# simCard.net
KiCad netlist of a schematic drawn in Altium Designer
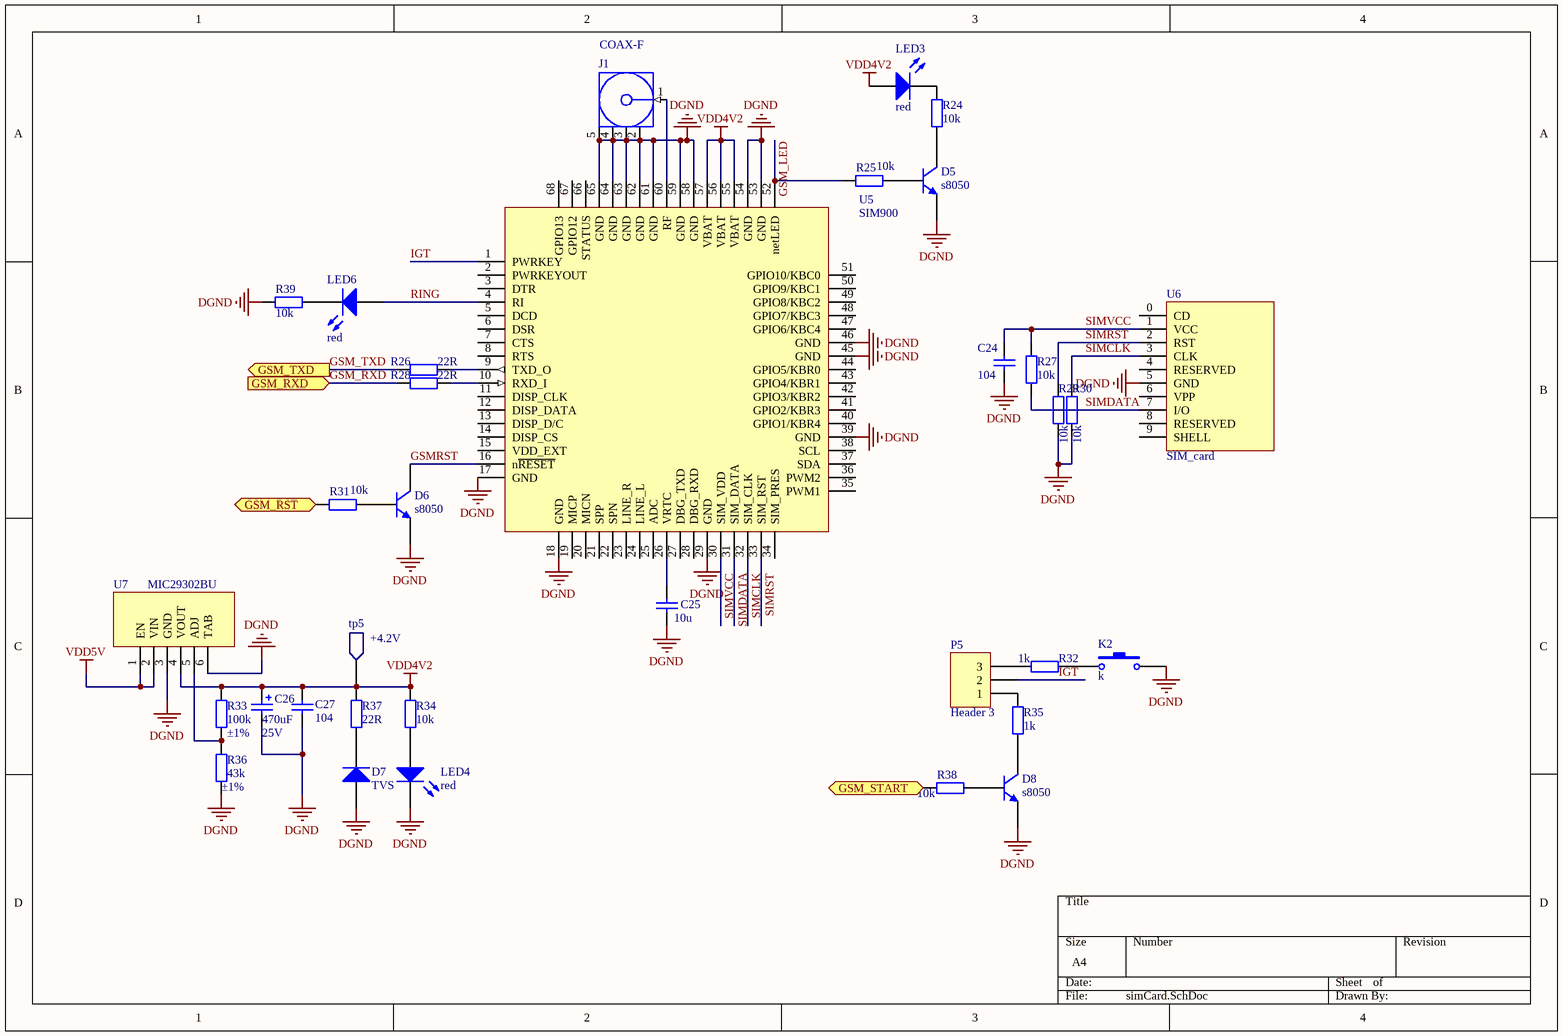
[diagram p0: simCard.SchDoc]

(export (version "E")
  (design (tool "Eeschema 10.0.6"))
  (components
    (comp (ref "C24") (value "104") (footprint "0603_") (libsource (lib "chxxlib") (part "cap")))
    (comp (ref "C25") (value "10u") (footprint "0603_") (libsource (lib "chxxlib") (part "cap")))
    (comp (ref "C26")
      (value "470uF")
      (footprint "Cap - 10mmx10mm")
      (fields (field (name "VDC_") "25V"))
      (libsource (lib "chxxlib") (part "cap-pol"))
    )
    (comp (ref "C27") (value "104") (footprint "0603_") (libsource (lib "chxxlib") (part "cap")))
    (comp (ref "D5") (value "s8050") (footprint "SOT-23(bce)") (libsource (lib "chxxlib") (part "NPN")))
    (comp (ref "D6") (value "s8050") (footprint "SOT-23(bce)") (libsource (lib "chxxlib") (part "NPN")))
    (comp (ref "D7") (value "TVS") (footprint "SMB") (libsource (lib "chxxlib") (part "diode")))
    (comp (ref "D8") (value "s8050") (footprint "SOT-23(bce)") (libsource (lib "chxxlib") (part "NPN")))
    (comp (ref "J1")
      (value "COAX-F")
      (footprint "MCX5.08-H5")
      (fields (field (name "PUBLISHER") "Altium Limited"))
      (libsource (lib "Miscellaneous Connectors") (part "COAX-F"))
    )
    (comp (ref "K2") (value "k") (footprint "key-2pin") (libsource (lib "chxxlib") (part "SW")))
    (comp (ref "LED3") (value "red") (footprint "0603_diode") (libsource (lib "chxxlib") (part "red")))
    (comp (ref "LED4") (value "red") (footprint "0603_diode") (libsource (lib "chxxlib") (part "red")))
    (comp (ref "LED6") (value "red") (footprint "0603_diode") (libsource (lib "chxxlib") (part "red")))
    (comp (ref "P5")
      (value "Header 3")
      (footprint "HDR1X3")
      (description "Header, 3-Pin")
      (fields (field (name "PUBLISHER") "Altium Limited"))
      (libsource (lib "Miscellaneous Connectors") (part "Header 3"))
    )
    (comp (ref "R24") (value "10k") (footprint "0603_") (libsource (lib "chxxlib") (part "res")))
    (comp (ref "R25") (value "10k") (footprint "0603_") (libsource (lib "") (part "res_2")))
    (comp (ref "R26") (value "22R") (footprint "0603_") (libsource (lib "") (part "res_1")))
    (comp (ref "R27") (value "10k") (footprint "0603_") (libsource (lib "chxxlib") (part "res")))
    (comp (ref "R28") (value "22R") (footprint "0603_") (libsource (lib "") (part "res_1")))
    (comp (ref "R29") (value "10k") (footprint "0603_") (libsource (lib "chxxlib") (part "res")))
    (comp (ref "R30") (value "10k") (footprint "0603_") (libsource (lib "chxxlib") (part "res")))
    (comp (ref "R31") (value "10k") (footprint "0603_") (libsource (lib "") (part "res_2")))
    (comp (ref "R32") (value "1k") (footprint "0603_") (libsource (lib "") (part "res_2")))
    (comp (ref "R33")
      (value "100k")
      (footprint "0603_")
      (fields (field (name "TOLERANCE_") "±1%"))
      (libsource (lib "chxxlib") (part "res"))
    )
    (comp (ref "R34") (value "10k") (footprint "0603_") (libsource (lib "chxxlib") (part "res")))
    (comp (ref "R35") (value "1k") (footprint "0603_") (libsource (lib "chxxlib") (part "res")))
    (comp (ref "R36")
      (value "43k")
      (footprint "0603_")
      (fields (field (name "TOLERANCE_") "±1%"))
      (libsource (lib "chxxlib") (part "res"))
    )
    (comp (ref "R37") (value "22R") (footprint "0603_") (libsource (lib "chxxlib") (part "res")))
    (comp (ref "R38") (value "10k") (footprint "0603_") (libsource (lib "") (part "res_2")))
    (comp (ref "R39") (value "10k") (footprint "0603_") (libsource (lib "") (part "res_1")))
    (comp (ref "tp5") (value "+4.2V") (footprint "testPoint") (libsource (lib "chxxlib") (part "pad")))
    (comp (ref "U5") (value "SIM900") (footprint "SIM900") (libsource (lib "chxxlib") (part "SIM900")))
    (comp (ref "U6") (value "SIM_card") (footprint "SIM_Card") (libsource (lib "chxxlib") (part "SIM_card")))
    (comp (ref "U7")
      (value "MIC29302BU")
      (footprint "TO-263(S)")
      (libsource (lib "chxxlib") (part "MIC29302BU"))
    )
  )
  (nets
    (net (code "1") (name "/GSMRST") (class "Default")
      (node (ref "D6") (pin "c") (pinfunction "C_c") (pintype "passive"))
      (node (ref "U5") (pin "16") (pinfunction "n~{RESET}_16") (pintype "passive"))
    )
    (net (code "2") (name "/GSM_LED") (class "Default")
      (node (ref "R25") (pin "2") (pinfunction "2_2") (pintype "passive"))
      (node (ref "U5") (pin "52") (pinfunction "netLED_52") (pintype "passive"))
    )
    (net (code "3") (name "/GSM_RST") (class "Default")
      (node (ref "R31") (pin "2") (pinfunction "2_2") (pintype "passive"))
    )
    (net (code "4") (name "/GSM_RXD") (class "Default")
      (node (ref "R28") (pin "1") (pinfunction "1_1") (pintype "passive"))
    )
    (net (code "5") (name "/GSM_START") (class "Default")
      (node (ref "R38") (pin "2") (pinfunction "2_2") (pintype "passive"))
    )
    (net (code "6") (name "/GSM_TXD") (class "Default")
      (node (ref "R26") (pin "1") (pinfunction "1_1") (pintype "passive"))
    )
    (net (code "7") (name "/IGT") (class "Default")
      (node (ref "P5") (pin "2") (pinfunction "2_2") (pintype "passive"))
      (node (ref "U5") (pin "1") (pinfunction "PWRKEY_1") (pintype "passive"))
    )
    (net (code "8") (name "/RING") (class "Default")
      (node (ref "LED6") (pin "1") (pinfunction "A_1") (pintype "passive"))
      (node (ref "U5") (pin "4") (pinfunction "RI_4") (pintype "passive"))
    )
    (net (code "9") (name "/SIMCLK") (class "Default")
      (node (ref "R30") (pin "2") (pinfunction "2_2") (pintype "passive"))
      (node (ref "U5") (pin "32") (pinfunction "SIM_CLK_32") (pintype "passive"))
      (node (ref "U6") (pin "3") (pinfunction "CLK_3") (pintype "passive"))
    )
    (net (code "10") (name "/SIMDATA") (class "Default")
      (node (ref "R27") (pin "1") (pinfunction "1_1") (pintype "passive"))
      (node (ref "U5") (pin "31") (pinfunction "SIM_DATA_31") (pintype "passive"))
      (node (ref "U6") (pin "7") (pinfunction "I/O_7") (pintype "passive"))
    )
    (net (code "11") (name "/SIMRST") (class "Default")
      (node (ref "R29") (pin "2") (pinfunction "2_2") (pintype "passive"))
      (node (ref "U5") (pin "33") (pinfunction "SIM_RST_33") (pintype "passive"))
      (node (ref "U6") (pin "2") (pinfunction "RST_2") (pintype "passive"))
    )
    (net (code "12") (name "/SIMVCC") (class "Default")
      (node (ref "C24") (pin "2") (pinfunction "2_2") (pintype "passive"))
      (node (ref "R27") (pin "2") (pinfunction "2_2") (pintype "passive"))
      (node (ref "U5") (pin "30") (pinfunction "SIM_VDD_30") (pintype "passive"))
      (node (ref "U6") (pin "1") (pinfunction "VCC_1") (pintype "passive"))
    )
    (net (code "13") (name "DGND") (class "Default")
      (node (ref "C24") (pin "1") (pinfunction "1_1") (pintype "passive"))
      (node (ref "C25") (pin "1") (pinfunction "1_1") (pintype "passive"))
      (node (ref "C26") (pin "2") (pinfunction "2_2") (pintype "passive"))
      (node (ref "C27") (pin "1") (pinfunction "1_1") (pintype "passive"))
      (node (ref "D5") (pin "e") (pinfunction "E_e") (pintype "passive"))
      (node (ref "D6") (pin "e") (pinfunction "E_e") (pintype "passive"))
      (node (ref "D7") (pin "A") (pinfunction "A_A") (pintype "passive"))
      (node (ref "D8") (pin "e") (pinfunction "E_e") (pintype "passive"))
      (node (ref "J1") (pin "2") (pinfunction "GND_2") (pintype "power_in"))
      (node (ref "J1") (pin "3") (pinfunction "GND_3") (pintype "power_in"))
      (node (ref "J1") (pin "4") (pinfunction "GND_4") (pintype "power_in"))
      (node (ref "J1") (pin "5") (pinfunction "GND_5") (pintype "power_in"))
      (node (ref "K2") (pin "2") (pinfunction "2_2") (pintype "passive"))
      (node (ref "LED4") (pin "2") (pinfunction "K_2") (pintype "passive"))
      (node (ref "R29") (pin "1") (pinfunction "1_1") (pintype "passive"))
      (node (ref "R30") (pin "1") (pinfunction "1_1") (pintype "passive"))
      (node (ref "R36") (pin "1") (pinfunction "1_1") (pintype "passive"))
      (node (ref "R39") (pin "1") (pinfunction "1_1") (pintype "passive"))
      (node (ref "U5") (pin "17") (pinfunction "GND_17") (pintype "passive"))
      (node (ref "U5") (pin "18") (pinfunction "GND_18") (pintype "passive"))
      (node (ref "U5") (pin "29") (pinfunction "GND_29") (pintype "passive"))
      (node (ref "U5") (pin "39") (pinfunction "GND_39") (pintype "passive"))
      (node (ref "U5") (pin "45") (pinfunction "GND_45") (pintype "passive"))
      (node (ref "U5") (pin "46") (pinfunction "GND_46") (pintype "passive"))
      (node (ref "U5") (pin "53") (pinfunction "GND_53") (pintype "passive"))
      (node (ref "U5") (pin "54") (pinfunction "GND_54") (pintype "passive"))
      (node (ref "U5") (pin "58") (pinfunction "GND_58") (pintype "passive"))
      (node (ref "U5") (pin "59") (pinfunction "GND_59") (pintype "passive"))
      (node (ref "U5") (pin "61") (pinfunction "GND_61") (pintype "passive"))
      (node (ref "U5") (pin "62") (pinfunction "GND_62") (pintype "passive"))
      (node (ref "U5") (pin "63") (pinfunction "GND_63") (pintype "passive"))
      (node (ref "U5") (pin "64") (pinfunction "GND_64") (pintype "passive"))
      (node (ref "U5") (pin "65") (pinfunction "GND_65") (pintype "passive"))
      (node (ref "U6") (pin "5") (pinfunction "GND_5") (pintype "passive"))
      (node (ref "U7") (pin "3") (pinfunction "GND_3") (pintype "passive"))
      (node (ref "U7") (pin "6") (pinfunction "TAB_6") (pintype "passive"))
    )
    (net (code "14") (name "Net-(D5-B)") (class "Default")
      (node (ref "D5") (pin "b") (pinfunction "B_b") (pintype "passive"))
      (node (ref "R25") (pin "1") (pinfunction "1_1") (pintype "passive"))
    )
    (net (code "15") (name "Net-(D5-C)") (class "Default")
      (node (ref "D5") (pin "c") (pinfunction "C_c") (pintype "passive"))
      (node (ref "R24") (pin "1") (pinfunction "1_1") (pintype "passive"))
    )
    (net (code "16") (name "Net-(D6-B)") (class "Default")
      (node (ref "D6") (pin "b") (pinfunction "B_b") (pintype "passive"))
      (node (ref "R31") (pin "1") (pinfunction "1_1") (pintype "passive"))
    )
    (net (code "17") (name "Net-(D7-PadK)") (class "Default")
      (node (ref "D7") (pin "K") (pinfunction "K_K") (pintype "passive"))
      (node (ref "R37") (pin "1") (pinfunction "1_1") (pintype "passive"))
    )
    (net (code "18") (name "Net-(D8-B)") (class "Default")
      (node (ref "D8") (pin "b") (pinfunction "B_b") (pintype "passive"))
      (node (ref "R38") (pin "1") (pinfunction "1_1") (pintype "passive"))
    )
    (net (code "19") (name "Net-(D8-C)") (class "Default")
      (node (ref "D8") (pin "c") (pinfunction "C_c") (pintype "passive"))
      (node (ref "R35") (pin "1") (pinfunction "1_1") (pintype "passive"))
    )
    (net (code "20") (name "Net-(J1-Signal)") (class "Default")
      (node (ref "J1") (pin "1") (pinfunction "Signal_1") (pintype "input"))
      (node (ref "U5") (pin "60") (pinfunction "RF_60") (pintype "passive"))
    )
    (net (code "21") (name "Net-(K2-Pad1)") (class "Default")
      (node (ref "K2") (pin "1") (pinfunction "1_1") (pintype "passive"))
      (node (ref "R32") (pin "1") (pinfunction "1_1") (pintype "passive"))
    )
    (net (code "22") (name "Net-(LED3-K)") (class "Default")
      (node (ref "LED3") (pin "2") (pinfunction "K_2") (pintype "passive"))
      (node (ref "R24") (pin "2") (pinfunction "2_2") (pintype "passive"))
    )
    (net (code "23") (name "Net-(LED4-A)") (class "Default")
      (node (ref "LED4") (pin "1") (pinfunction "A_1") (pintype "passive"))
      (node (ref "R34") (pin "1") (pinfunction "1_1") (pintype "passive"))
    )
    (net (code "24") (name "Net-(LED6-K)") (class "Default")
      (node (ref "LED6") (pin "2") (pinfunction "K_2") (pintype "passive"))
      (node (ref "R39") (pin "2") (pinfunction "2_2") (pintype "passive"))
    )
    (net (code "25") (name "Net-(P5-Pad1)") (class "Default")
      (node (ref "P5") (pin "1") (pinfunction "1_1") (pintype "passive"))
      (node (ref "R35") (pin "2") (pinfunction "2_2") (pintype "passive"))
    )
    (net (code "26") (name "Net-(P5-Pad3)") (class "Default")
      (node (ref "P5") (pin "3") (pinfunction "3_3") (pintype "passive"))
      (node (ref "R32") (pin "2") (pinfunction "2_2") (pintype "passive"))
    )
    (net (code "27") (name "Net-(U5-RXD_I)") (class "Default")
      (node (ref "R28") (pin "2") (pinfunction "2_2") (pintype "passive"))
      (node (ref "U5") (pin "10") (pinfunction "RXD_I_10") (pintype "input"))
    )
    (net (code "28") (name "Net-(U5-TXD_O)") (class "Default")
      (node (ref "R26") (pin "2") (pinfunction "2_2") (pintype "passive"))
      (node (ref "U5") (pin "9") (pinfunction "TXD_O_9") (pintype "output"))
    )
    (net (code "29") (name "Net-(U5-VRTC)") (class "Default")
      (node (ref "C25") (pin "2") (pinfunction "2_2") (pintype "passive"))
      (node (ref "U5") (pin "26") (pinfunction "VRTC_26") (pintype "passive"))
    )
    (net (code "30") (name "Net-(U7-ADJ)") (class "Default")
      (node (ref "R33") (pin "1") (pinfunction "1_1") (pintype "passive"))
      (node (ref "R36") (pin "2") (pinfunction "2_2") (pintype "passive"))
      (node (ref "U7") (pin "5") (pinfunction "ADJ_5") (pintype "passive"))
    )
    (net (code "31") (name "VDD4V2") (class "Default")
      (node (ref "C26") (pin "1") (pinfunction "1_1") (pintype "passive"))
      (node (ref "C27") (pin "2") (pinfunction "2_2") (pintype "passive"))
      (node (ref "LED3") (pin "1") (pinfunction "A_1") (pintype "passive"))
      (node (ref "R33") (pin "2") (pinfunction "2_2") (pintype "passive"))
      (node (ref "R34") (pin "2") (pinfunction "2_2") (pintype "passive"))
      (node (ref "R37") (pin "2") (pinfunction "2_2") (pintype "passive"))
      (node (ref "U5") (pin "55") (pinfunction "VBAT_55") (pintype "passive"))
      (node (ref "U5") (pin "56") (pinfunction "VBAT_56") (pintype "passive"))
      (node (ref "U5") (pin "57") (pinfunction "VBAT_57") (pintype "passive"))
      (node (ref "U7") (pin "4") (pinfunction "VOUT_4") (pintype "passive"))
      (node (ref "tp5") (pin "1") (pinfunction "1_1") (pintype "power_in"))
    )
    (net (code "32") (name "VDD5V") (class "Default")
      (node (ref "U7") (pin "1") (pinfunction "EN_1") (pintype "passive"))
      (node (ref "U7") (pin "2") (pinfunction "VIN_2") (pintype "passive"))
    )
    (net (code "33") (name "unconnected-(U5-ADC-Pad25)") (class "Default")
      (node (ref "U5") (pin "25") (pinfunction "ADC_25") (pintype "passive"))
    )
    (net (code "34") (name "unconnected-(U5-CTS-Pad7)") (class "Default")
      (node (ref "U5") (pin "7") (pinfunction "CTS_7") (pintype "passive"))
    )
    (net (code "35") (name "unconnected-(U5-DBG_RXD-Pad28)") (class "Default")
      (node (ref "U5") (pin "28") (pinfunction "DBG_RXD_28") (pintype "passive"))
    )
    (net (code "36") (name "unconnected-(U5-DBG_TXD-Pad27)") (class "Default")
      (node (ref "U5") (pin "27") (pinfunction "DBG_TXD_27") (pintype "passive"))
    )
    (net (code "37") (name "unconnected-(U5-DCD-Pad5)") (class "Default")
      (node (ref "U5") (pin "5") (pinfunction "DCD_5") (pintype "passive"))
    )
    (net (code "38") (name "unconnected-(U5-DISP_CLK-Pad11)") (class "Default")
      (node (ref "U5") (pin "11") (pinfunction "DISP_CLK_11") (pintype "passive"))
    )
    (net (code "39") (name "unconnected-(U5-DISP_CS-Pad14)") (class "Default")
      (node (ref "U5") (pin "14") (pinfunction "DISP_CS_14") (pintype "passive"))
    )
    (net (code "40") (name "unconnected-(U5-DISP_DATA-Pad12)") (class "Default")
      (node (ref "U5") (pin "12") (pinfunction "DISP_DATA_12") (pintype "passive"))
    )
    (net (code "41") (name "unconnected-(U5-DISP_D{slash}C-Pad13)") (class "Default")
      (node (ref "U5") (pin "13") (pinfunction "DISP_D/C_13") (pintype "passive"))
    )
    (net (code "42") (name "unconnected-(U5-DSR-Pad6)") (class "Default")
      (node (ref "U5") (pin "6") (pinfunction "DSR_6") (pintype "passive"))
    )
    (net (code "43") (name "unconnected-(U5-DTR-Pad3)") (class "Default")
      (node (ref "U5") (pin "3") (pinfunction "DTR_3") (pintype "passive"))
    )
    (net (code "44") (name "unconnected-(U5-GPIO1{slash}KBR4-Pad40)") (class "Default")
      (node (ref "U5") (pin "40") (pinfunction "GPIO1/KBR4_40") (pintype "passive"))
    )
    (net (code "45") (name "unconnected-(U5-GPIO2{slash}KBR3-Pad41)") (class "Default")
      (node (ref "U5") (pin "41") (pinfunction "GPIO2/KBR3_41") (pintype "passive"))
    )
    (net (code "46") (name "unconnected-(U5-GPIO3{slash}KBR2-Pad42)") (class "Default")
      (node (ref "U5") (pin "42") (pinfunction "GPIO3/KBR2_42") (pintype "passive"))
    )
    (net (code "47") (name "unconnected-(U5-GPIO4{slash}KBR1-Pad43)") (class "Default")
      (node (ref "U5") (pin "43") (pinfunction "GPIO4/KBR1_43") (pintype "passive"))
    )
    (net (code "48") (name "unconnected-(U5-GPIO5{slash}KBR0-Pad44)") (class "Default")
      (node (ref "U5") (pin "44") (pinfunction "GPIO5/KBR0_44") (pintype "passive"))
    )
    (net (code "49") (name "unconnected-(U5-GPIO6{slash}KBC4-Pad47)") (class "Default")
      (node (ref "U5") (pin "47") (pinfunction "GPIO6/KBC4_47") (pintype "passive"))
    )
    (net (code "50") (name "unconnected-(U5-GPIO7{slash}KBC3-Pad48)") (class "Default")
      (node (ref "U5") (pin "48") (pinfunction "GPIO7/KBC3_48") (pintype "passive"))
    )
    (net (code "51") (name "unconnected-(U5-GPIO8{slash}KBC2-Pad49)") (class "Default")
      (node (ref "U5") (pin "49") (pinfunction "GPIO8/KBC2_49") (pintype "passive"))
    )
    (net (code "52") (name "unconnected-(U5-GPIO9{slash}KBC1-Pad50)") (class "Default")
      (node (ref "U5") (pin "50") (pinfunction "GPIO9/KBC1_50") (pintype "passive"))
    )
    (net (code "53") (name "unconnected-(U5-GPIO10{slash}KBC0-Pad51)") (class "Default")
      (node (ref "U5") (pin "51") (pinfunction "GPIO10/KBC0_51") (pintype "passive"))
    )
    (net (code "54") (name "unconnected-(U5-GPIO12-Pad67)") (class "Default")
      (node (ref "U5") (pin "67") (pinfunction "GPIO12_67") (pintype "passive"))
    )
    (net (code "55") (name "unconnected-(U5-GPIO13-Pad68)") (class "Default")
      (node (ref "U5") (pin "68") (pinfunction "GPIO13_68") (pintype "passive"))
    )
    (net (code "56") (name "unconnected-(U5-LINE_L-Pad24)") (class "Default")
      (node (ref "U5") (pin "24") (pinfunction "LINE_L_24") (pintype "passive"))
    )
    (net (code "57") (name "unconnected-(U5-LINE_R-Pad23)") (class "Default")
      (node (ref "U5") (pin "23") (pinfunction "LINE_R_23") (pintype "passive"))
    )
    (net (code "58") (name "unconnected-(U5-MICN-Pad20)") (class "Default")
      (node (ref "U5") (pin "20") (pinfunction "MICN_20") (pintype "passive"))
    )
    (net (code "59") (name "unconnected-(U5-MICP-Pad19)") (class "Default")
      (node (ref "U5") (pin "19") (pinfunction "MICP_19") (pintype "passive"))
    )
    (net (code "60") (name "unconnected-(U5-PWM1-Pad35)") (class "Default")
      (node (ref "U5") (pin "35") (pinfunction "PWM1_35") (pintype "passive"))
    )
    (net (code "61") (name "unconnected-(U5-PWM2-Pad36)") (class "Default")
      (node (ref "U5") (pin "36") (pinfunction "PWM2_36") (pintype "passive"))
    )
    (net (code "62") (name "unconnected-(U5-PWRKEYOUT-Pad2)") (class "Default")
      (node (ref "U5") (pin "2") (pinfunction "PWRKEYOUT_2") (pintype "passive"))
    )
    (net (code "63") (name "unconnected-(U5-RTS-Pad8)") (class "Default")
      (node (ref "U5") (pin "8") (pinfunction "RTS_8") (pintype "passive"))
    )
    (net (code "64") (name "unconnected-(U5-SCL-Pad38)") (class "Default")
      (node (ref "U5") (pin "38") (pinfunction "SCL_38") (pintype "passive"))
    )
    (net (code "65") (name "unconnected-(U5-SDA-Pad37)") (class "Default")
      (node (ref "U5") (pin "37") (pinfunction "SDA_37") (pintype "passive"))
    )
    (net (code "66") (name "unconnected-(U5-SIM_PRES-Pad34)") (class "Default")
      (node (ref "U5") (pin "34") (pinfunction "SIM_PRES_34") (pintype "passive"))
    )
    (net (code "67") (name "unconnected-(U5-SPN-Pad22)") (class "Default")
      (node (ref "U5") (pin "22") (pinfunction "SPN_22") (pintype "passive"))
    )
    (net (code "68") (name "unconnected-(U5-SPP-Pad21)") (class "Default")
      (node (ref "U5") (pin "21") (pinfunction "SPP_21") (pintype "passive"))
    )
    (net (code "69") (name "unconnected-(U5-STATUS-Pad66)") (class "Default")
      (node (ref "U5") (pin "66") (pinfunction "STATUS_66") (pintype "passive"))
    )
    (net (code "70") (name "unconnected-(U5-VDD_EXT-Pad15)") (class "Default")
      (node (ref "U5") (pin "15") (pinfunction "VDD_EXT_15") (pintype "passive"))
    )
    (net (code "71") (name "unconnected-(U6-CD-Pad0)") (class "Default")
      (node (ref "U6") (pin "0") (pinfunction "CD_0") (pintype "passive"))
    )
    (net (code "72") (name "unconnected-(U6-RESERVED-Pad4)") (class "Default")
      (node (ref "U6") (pin "4") (pinfunction "RESERVED_4") (pintype "passive"))
    )
    (net (code "73") (name "unconnected-(U6-RESERVED-Pad8)") (class "Default")
      (node (ref "U6") (pin "8") (pinfunction "RESERVED_8") (pintype "passive"))
    )
    (net (code "74") (name "unconnected-(U6-SHELL-Pad9)") (class "Default")
      (node (ref "U6") (pin "9") (pinfunction "SHELL_9") (pintype "passive"))
    )
    (net (code "75") (name "unconnected-(U6-VPP-Pad6)") (class "Default")
      (node (ref "U6") (pin "6") (pinfunction "VPP_6") (pintype "passive"))
    )
  )
)
